# DB_ECG-X01.net
KiCad netlist of a schematic drawn in Altium Designer
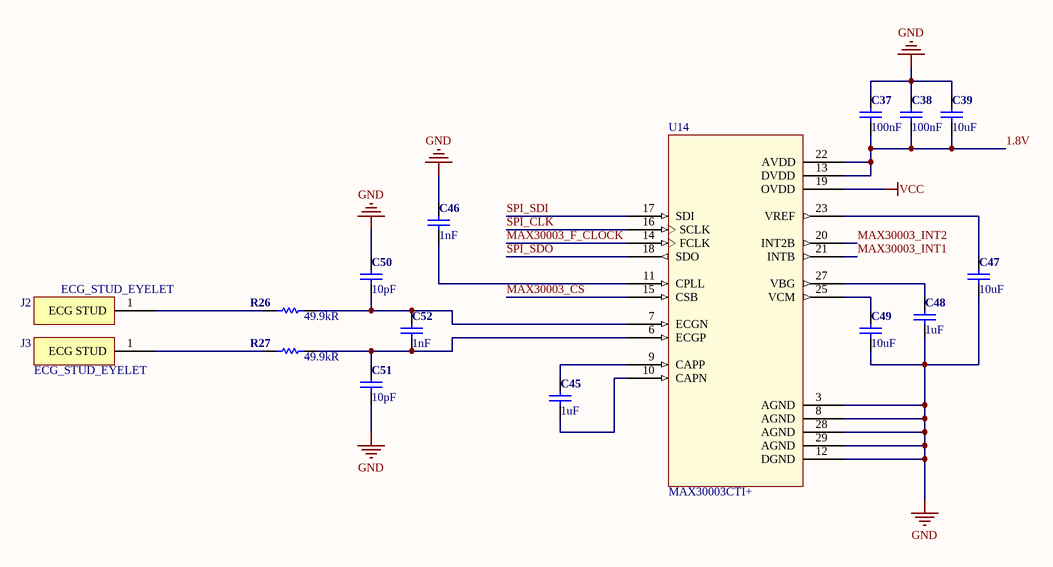
[diagram p0: DB_ECG-X01.SchDoc]

(export (version "E")
  (design (tool "Eeschema 10.0.6"))
  (components
    (comp (ref "C37")
      (value "100nF")
      (footprint "C0603")
      (fields
        (field (name "MANUFACTURER") "Yageo")
        (field (name "MANUFACTURER PART NUMBER") "CC0402ZRY5V8BB104")
        (field (name "TOLERANCE") "80%")
      )
      (libsource (lib "DB-X01") (part "C-0603(1608)"))
    )
    (comp (ref "C38")
      (value "100nF")
      (footprint "C0603")
      (fields
        (field (name "MANUFACTURER") "Yageo")
        (field (name "MANUFACTURER PART NUMBER") "CC0402ZRY5V8BB104")
        (field (name "TOLERANCE") "80%")
      )
      (libsource (lib "DB-X01") (part "C-0603(1608)"))
    )
    (comp (ref "C39")
      (value "10uF")
      (footprint "C0603")
      (fields
        (field (name "MANUFACTURER") "Murata")
        (field (name "MANUFACTURER PART NUMBER") "GRM188R61E106MA73J")
        (field (name "TOLERANCE") "20%")
      )
      (libsource (lib "DB-X01") (part "C-0603(1608)"))
    )
    (comp (ref "C45")
      (value "1uF")
      (footprint "C0402")
      (fields
        (field (name "MANUFACTURER") "Yageo")
        (field (name "MANUFACTURER PART NUMBER") "CC0402MRX5R5BB105")
        (field (name "TOLERANCE") "20%")
      )
      (libsource (lib "DB-X01") (part "C-0402(1005)"))
    )
    (comp (ref "C46")
      (value "1nF")
      (footprint "C0402")
      (description "Ceramic Capacitor, Multilayer, Ceramic, 10V, 5% +Tol, 5% -Tol, C0G, -/+30ppm/Cel TC, 0.001uF, 0402")
      (fields
        (field (name "MANUFACTURER") "KEMET")
        (field (name "MANUFACTURER PART NUMBER") "C0402C102J8GAC7867")
      )
      (libsource (lib "DB-X01") (part "C-0402(1005)"))
    )
    (comp (ref "C47")
      (value "10uF")
      (footprint "C0603")
      (fields
        (field (name "MANUFACTURER") "Murata")
        (field (name "MANUFACTURER PART NUMBER") "GRM188R61E106MA73J")
        (field (name "TOLERANCE") "20%")
      )
      (libsource (lib "DB-X01") (part "C-0603(1608)"))
    )
    (comp (ref "C48")
      (value "1uF")
      (footprint "C0402")
      (fields
        (field (name "MANUFACTURER") "Yageo")
        (field (name "MANUFACTURER PART NUMBER") "CC0402MRX5R5BB105")
        (field (name "TOLERANCE") "20%")
      )
      (libsource (lib "DB-X01") (part "C-0402(1005)"))
    )
    (comp (ref "C49")
      (value "10uF")
      (footprint "C0603")
      (fields
        (field (name "MANUFACTURER") "Murata")
        (field (name "MANUFACTURER PART NUMBER") "GRM188R61E106MA73J")
        (field (name "TOLERANCE") "20%")
      )
      (libsource (lib "DB-X01") (part "C-0603(1608)"))
    )
    (comp (ref "C50")
      (value "10pF")
      (footprint "C0402")
      (fields
        (field (name "MANUFACTURER") "Murata")
        (field (name "MANUFACTURER PART NUMBER") "GJM1555C1H100JB01D")
        (field (name "TOLERANCE") "5%")
      )
      (libsource (lib "DB-X01") (part "C-0402(1005)"))
    )
    (comp (ref "C51")
      (value "10pF")
      (footprint "C0402")
      (fields
        (field (name "MANUFACTURER") "Murata")
        (field (name "MANUFACTURER PART NUMBER") "GJM1555C1H100JB01D")
        (field (name "TOLERANCE") "5%")
      )
      (libsource (lib "DB-X01") (part "C-0402(1005)"))
    )
    (comp (ref "C52")
      (value "1nF")
      (footprint "C0402")
      (description "Ceramic Capacitor, Multilayer, Ceramic, 10V, 5% +Tol, 5% -Tol, C0G, -/+30ppm/Cel TC, 0.001uF, 0402")
      (fields
        (field (name "MANUFACTURER") "KEMET")
        (field (name "MANUFACTURER PART NUMBER") "C0402C102J8GAC7867")
      )
      (libsource (lib "DB-X01") (part "C-0402(1005)"))
    )
    (comp (ref "J2")
      (value "ECG_STUD_EYELET")
      (footprint "ECG_STUD")
      (libsource (lib "DB-X01") (part "ECG_STUD_EYELET"))
    )
    (comp (ref "J3")
      (value "ECG_STUD_EYELET")
      (footprint "ECG_STUD")
      (libsource (lib "DB-X01") (part "ECG_STUD_EYELET"))
    )
    (comp (ref "R26")
      (value "49.9kR")
      (footprint "R0402")
      (fields
        (field (name "MANUFACTURER") "Yageo")
        (field (name "MANUFACTURER PART NUMBER") "AC0402FR-0749K9L")
        (field (name "TOLERANCE") "1%")
      )
      (libsource (lib "DB-X01") (part "R-0402(1005)"))
    )
    (comp (ref "R27")
      (value "49.9kR")
      (footprint "R0402")
      (fields
        (field (name "MANUFACTURER") "Yageo")
        (field (name "MANUFACTURER PART NUMBER") "AC0402FR-0749K9L")
        (field (name "TOLERANCE") "1%")
      )
      (libsource (lib "DB-X01") (part "R-0402(1005)"))
    )
    (comp (ref "U14")
      (value "MAX30003CTI+")
      (footprint "QFN50P500X500X80-29N")
      (description "Analog Circuit, 1 Func, CMOS")
      (fields (field (name "MANUFACTURER") "Maxim"))
      (libsource (lib "DB-X01") (part "MAX30003CTI+"))
    )
  )
  (nets
    (net (code "1") (name "/1.8V") (class "Default")
      (node (ref "C37") (pin "1") (pinfunction "1_1") (pintype "passive"))
      (node (ref "C38") (pin "1") (pinfunction "1_1") (pintype "passive"))
      (node (ref "C39") (pin "1") (pinfunction "1_1") (pintype "passive"))
      (node (ref "U14") (pin "13") (pinfunction "DVDD_13") (pintype "power_in"))
      (node (ref "U14") (pin "22") (pinfunction "AVDD_22") (pintype "power_in"))
    )
    (net (code "2") (name "/MAX30003_CS") (class "Default")
      (node (ref "U14") (pin "15") (pinfunction "CSB_15") (pintype "input"))
    )
    (net (code "3") (name "/MAX30003_F_CLOCK") (class "Default")
      (node (ref "U14") (pin "14") (pinfunction "FCLK_14") (pintype "input"))
    )
    (net (code "4") (name "/MAX30003_INT1") (class "Default")
      (node (ref "U14") (pin "21") (pinfunction "INTB_21") (pintype "output"))
    )
    (net (code "5") (name "/MAX30003_INT2") (class "Default")
      (node (ref "U14") (pin "20") (pinfunction "INT2B_20") (pintype "output"))
    )
    (net (code "6") (name "/SPI_CLK") (class "Default")
      (node (ref "U14") (pin "16") (pinfunction "SCLK_16") (pintype "input"))
    )
    (net (code "7") (name "/SPI_SDI") (class "Default")
      (node (ref "U14") (pin "17") (pinfunction "SDI_17") (pintype "input"))
    )
    (net (code "8") (name "/SPI_SDO") (class "Default")
      (node (ref "U14") (pin "18") (pinfunction "SDO_18") (pintype "output"))
    )
    (net (code "9") (name "GND") (class "Default")
      (node (ref "C37") (pin "2") (pinfunction "2_2") (pintype "passive"))
      (node (ref "C38") (pin "2") (pinfunction "2_2") (pintype "passive"))
      (node (ref "C39") (pin "2") (pinfunction "2_2") (pintype "passive"))
      (node (ref "C46") (pin "1") (pinfunction "1_1") (pintype "passive"))
      (node (ref "C47") (pin "1") (pinfunction "1_1") (pintype "passive"))
      (node (ref "C48") (pin "2") (pinfunction "2_2") (pintype "passive"))
      (node (ref "C49") (pin "1") (pinfunction "1_1") (pintype "passive"))
      (node (ref "C50") (pin "1") (pinfunction "1_1") (pintype "passive"))
      (node (ref "C51") (pin "2") (pinfunction "2_2") (pintype "passive"))
      (node (ref "U14") (pin "12") (pinfunction "DGND_12") (pintype "power_in"))
      (node (ref "U14") (pin "28") (pinfunction "AGND_28") (pintype "power_in"))
      (node (ref "U14") (pin "29") (pinfunction "AGND_29") (pintype "power_in"))
      (node (ref "U14") (pin "3") (pinfunction "AGND_3") (pintype "power_in"))
      (node (ref "U14") (pin "8") (pinfunction "AGND_8") (pintype "power_in"))
    )
    (net (code "10") (name "Net-(J2-ECG_STUD)") (class "Default")
      (node (ref "J2") (pin "1") (pinfunction "ECG_STUD_1") (pintype "passive"))
      (node (ref "R26") (pin "1") (pinfunction "1_1") (pintype "passive"))
    )
    (net (code "11") (name "Net-(J3-ECG_STUD)") (class "Default")
      (node (ref "J3") (pin "1") (pinfunction "ECG_STUD_1") (pintype "passive"))
      (node (ref "R27") (pin "1") (pinfunction "1_1") (pintype "passive"))
    )
    (net (code "12") (name "Net-(U14-CAPN)") (class "Default")
      (node (ref "C45") (pin "2") (pinfunction "2_2") (pintype "passive"))
      (node (ref "U14") (pin "10") (pinfunction "CAPN_10") (pintype "input"))
    )
    (net (code "13") (name "Net-(U14-CAPP)") (class "Default")
      (node (ref "C45") (pin "1") (pinfunction "1_1") (pintype "passive"))
      (node (ref "U14") (pin "9") (pinfunction "CAPP_9") (pintype "input"))
    )
    (net (code "14") (name "Net-(U14-CPLL)") (class "Default")
      (node (ref "C46") (pin "2") (pinfunction "2_2") (pintype "passive"))
      (node (ref "U14") (pin "11") (pinfunction "CPLL_11") (pintype "input"))
    )
    (net (code "15") (name "Net-(U14-ECGN)") (class "Default")
      (node (ref "C50") (pin "2") (pinfunction "2_2") (pintype "passive"))
      (node (ref "C52") (pin "1") (pinfunction "1_1") (pintype "passive"))
      (node (ref "R26") (pin "2") (pinfunction "2_2") (pintype "passive"))
      (node (ref "U14") (pin "7") (pinfunction "ECGN_7") (pintype "input"))
    )
    (net (code "16") (name "Net-(U14-ECGP)") (class "Default")
      (node (ref "C51") (pin "1") (pinfunction "1_1") (pintype "passive"))
      (node (ref "C52") (pin "2") (pinfunction "2_2") (pintype "passive"))
      (node (ref "R27") (pin "2") (pinfunction "2_2") (pintype "passive"))
      (node (ref "U14") (pin "6") (pinfunction "ECGP_6") (pintype "input"))
    )
    (net (code "17") (name "Net-(U14-VBG)") (class "Default")
      (node (ref "C48") (pin "1") (pinfunction "1_1") (pintype "passive"))
      (node (ref "U14") (pin "27") (pinfunction "VBG_27") (pintype "output"))
    )
    (net (code "18") (name "Net-(U14-VCM)") (class "Default")
      (node (ref "C49") (pin "2") (pinfunction "2_2") (pintype "passive"))
      (node (ref "U14") (pin "25") (pinfunction "VCM_25") (pintype "output"))
    )
    (net (code "19") (name "Net-(U14-VREF)") (class "Default")
      (node (ref "C47") (pin "2") (pinfunction "2_2") (pintype "passive"))
      (node (ref "U14") (pin "23") (pinfunction "VREF_23") (pintype "output"))
    )
    (net (code "20") (name "VCC") (class "Default")
      (node (ref "U14") (pin "19") (pinfunction "OVDD_19") (pintype "power_in"))
    )
  )
)
